# Half_bridge.net
KiCad netlist of a schematic drawn in Altium Designer
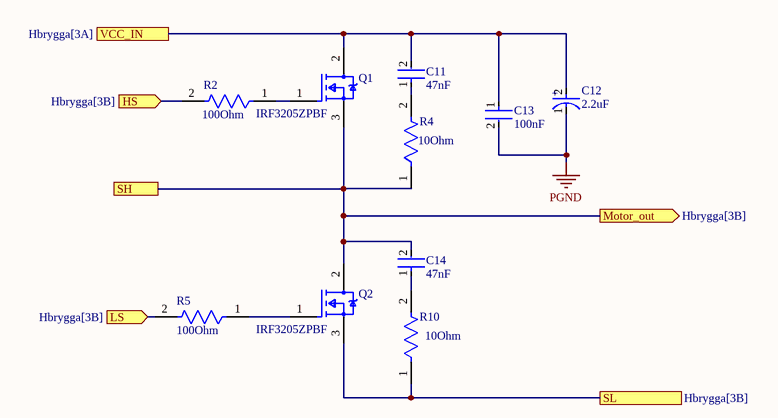
[diagram p0: Half_bridge.SchDoc]

(export (version "E")
  (design (tool "Eeschema 10.0.6"))
  (components
    (comp (ref "C11")
      (value "47nF")
      (footprint "FP-C1206C-EB-MFG")
      (description "C1206 47,000 pF X8R 20.00% 50 V")
      (fields
        (field (name "MANUFACTURER PART NUMBER") "C1206C473M5HAC")
        (field (name "OCTOPART") "https://octopart.com/c1206c473m5hac-kemet-98183372")
      )
      (libsource (lib "Altium Content Vault") (part "b4654b650e69147ec39a6b967a45e02"))
    )
    (comp (ref "C12")
      (value "2.2uF")
      (footprint "FP-RAD-TH-D_5_0_5-L_11_1-MFG")
      (description "Aluminum Electrolytic Capacitors (Radial Lead Type) 2.2uF ±20% 100V")
      (fields (field (name "VOLTAGE") "63V") (field (name "TOLERANCE") "20%"))
      (libsource (lib "Altium Content Vault") (part "a00bbbee19879c290e62620ae7e47b1"))
    )
    (comp (ref "C13")
      (value "100nF")
      (footprint "FP-C1206C-EB-MFG")
      (description "C1206 0.10 μF U2J 2.00% 16 V")
      (fields
        (field (name "MANUFACTURER PART NUMBER") "C1206C104G4JACAUTO")
        (field (name "TOLERANCE") "0.02")
      )
      (libsource (lib "Altium Content Vault") (part "b4654b650e69147ec39a6b967a45e02"))
    )
    (comp (ref "C14")
      (value "47nF")
      (footprint "FP-C1206C-EB-MFG")
      (description "C1206 47,000 pF X8R 20.00% 50 V")
      (fields
        (field (name "MANUFACTURER PART NUMBER") "C1206C473M5HAC")
        (field (name "OCTOPART") "https://octopart.com/c1206c473m5hac-kemet-98183372")
      )
      (libsource (lib "Altium Content Vault") (part "b4654b650e69147ec39a6b967a45e02"))
    )
    (comp (ref "Q1")
      (value "IRF3205ZPBF")
      (footprint "FP-PG-TO220-3-MFG")
      (description "MOSFET N-CH 55V 75A TO220AB")
      (libsource (lib "Altium Content Vault") (part "535c4fe1372f32a24686ada0a8c11ba"))
    )
    (comp (ref "Q2")
      (value "IRF3205ZPBF")
      (footprint "FP-PG-TO220-3-MFG")
      (description "MOSFET N-CH 55V 75A TO220AB")
      (libsource (lib "Altium Content Vault") (part "535c4fe1372f32a24686ada0a8c11ba"))
    )
    (comp (ref "R2")
      (value "100Ohm")
      (footprint "FP-AT1206-IPC_A")
      (description "Thin Film Chip Resistors Automotive Grade 100Ω 0.1% 10ppm/°C 1206")
      (libsource (lib "Altium Content Vault") (part "1029c3af85768c4190bb7ad29bc67b5"))
    )
    (comp (ref "R4")
      (value "10Ohm")
      (footprint "FP-AT1206-IPC_B")
      (description "Thin Film Chip Resistors Automotive Grade 10Ω 0.1% 25ppm/°C 1206")
      (fields (field (name "TOLERANCE") "0.1%"))
      (libsource (lib "Altium Content Vault") (part "1029c3af85768c4190bb7ad29bc67b5"))
    )
    (comp (ref "R5")
      (value "100Ohm")
      (footprint "FP-AT1206-IPC_A")
      (description "Thin Film Chip Resistors Automotive Grade 100Ω 0.1% 10ppm/°C 1206")
      (libsource (lib "Altium Content Vault") (part "1029c3af85768c4190bb7ad29bc67b5"))
    )
    (comp (ref "R10")
      (value "10Ohm")
      (footprint "FP-AT1206-IPC_B")
      (description "Thin Film Chip Resistors Automotive Grade 10Ω 0.1% 25ppm/°C 1206")
      (fields (field (name "TOLERANCE") "0.1%"))
      (libsource (lib "Altium Content Vault") (part "1029c3af85768c4190bb7ad29bc67b5"))
    )
  )
  (nets
    (net (code "1") (name "/HS") (class "Default")
      (node (ref "R2") (pin "2") (pinfunction "2_2") (pintype "passive"))
    )
    (net (code "2") (name "/LS") (class "Default")
      (node (ref "R5") (pin "2") (pinfunction "2_2") (pintype "passive"))
    )
    (net (code "3") (name "/Motor_out") (class "Default")
      (node (ref "C14") (pin "2") (pinfunction "2_2") (pintype "passive"))
      (node (ref "Q1") (pin "3") (pinfunction "S_3") (pintype "passive"))
      (node (ref "Q2") (pin "2") (pinfunction "D_2") (pintype "passive"))
      (node (ref "R4") (pin "1") (pinfunction "1_1") (pintype "passive"))
    )
    (net (code "4") (name "/SL") (class "Default")
      (node (ref "Q2") (pin "3") (pinfunction "S_3") (pintype "passive"))
      (node (ref "R10") (pin "1") (pinfunction "1_1") (pintype "passive"))
    )
    (net (code "5") (name "/VCC_IN") (class "Default")
      (node (ref "C11") (pin "2") (pinfunction "2_2") (pintype "passive"))
      (node (ref "C12") (pin "2") (pinfunction "A_2") (pintype "passive"))
      (node (ref "C13") (pin "1") (pinfunction "1_1") (pintype "passive"))
      (node (ref "Q1") (pin "2") (pinfunction "D_2") (pintype "passive"))
    )
    (net (code "6") (name "Net-(C11-Pad1)") (class "Default")
      (node (ref "C11") (pin "1") (pinfunction "1_1") (pintype "passive"))
      (node (ref "R4") (pin "2") (pinfunction "2_2") (pintype "passive"))
    )
    (net (code "7") (name "Net-(C14-Pad1)") (class "Default")
      (node (ref "C14") (pin "1") (pinfunction "1_1") (pintype "passive"))
      (node (ref "R10") (pin "2") (pinfunction "2_2") (pintype "passive"))
    )
    (net (code "8") (name "Net-(Q1-G)") (class "Default")
      (node (ref "Q1") (pin "1") (pinfunction "G_1") (pintype "passive"))
      (node (ref "R2") (pin "1") (pinfunction "1_1") (pintype "passive"))
    )
    (net (code "9") (name "Net-(Q2-G)") (class "Default")
      (node (ref "Q2") (pin "1") (pinfunction "G_1") (pintype "passive"))
      (node (ref "R5") (pin "1") (pinfunction "1_1") (pintype "passive"))
    )
    (net (code "10") (name "PGND") (class "Default")
      (node (ref "C12") (pin "1") (pinfunction "C_1") (pintype "passive"))
      (node (ref "C13") (pin "2") (pinfunction "2_2") (pintype "passive"))
    )
  )
)
